# stepper.net
KiCad netlist of a schematic drawn in Altium Designer
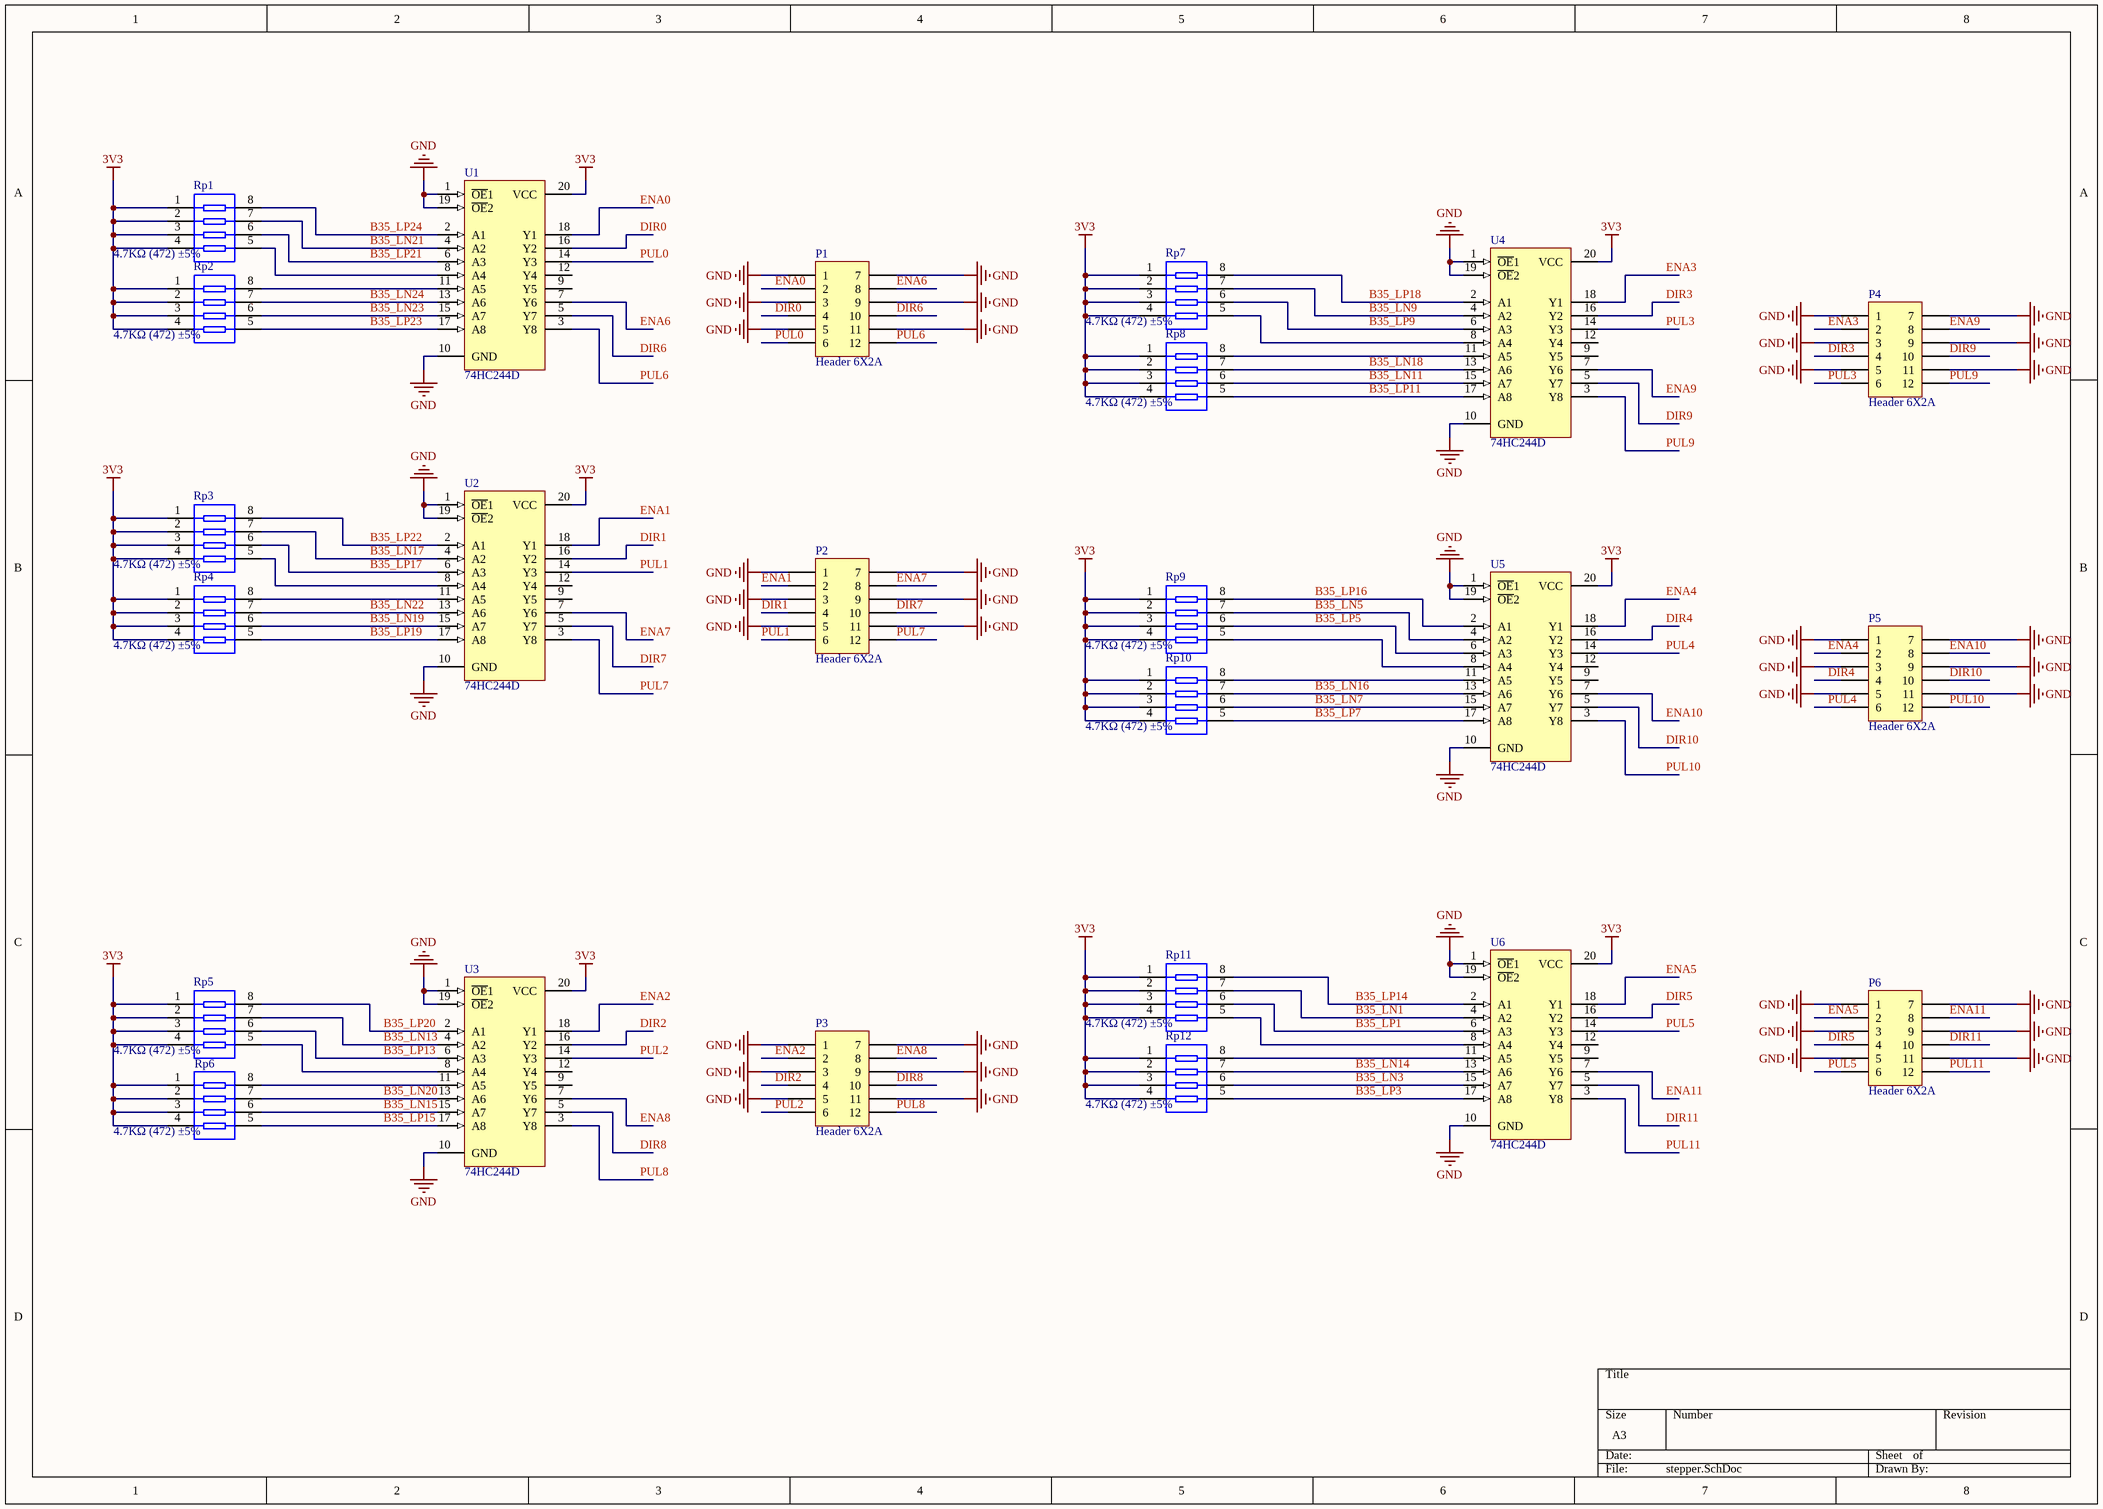
[diagram p0: stepper.SchDoc]

(export (version "E")
  (design (tool "Eeschema 10.0.6"))
  (components
    (comp (ref "P1")
      (value "Header 6X2A")
      (footprint "2EDG-3.81-06P*2 - duplicate")
      (description "Header, 6-Pin, Dual row")
      (fields (field (name "PUBLISHER") "Altium Limited"))
      (libsource (lib "Miscellaneous Connectors") (part "Header 6X2A"))
    )
    (comp (ref "P2")
      (value "Header 6X2A")
      (footprint "2EDG-3.81-06P*2 - duplicate")
      (description "Header, 6-Pin, Dual row")
      (fields (field (name "PUBLISHER") "Altium Limited"))
      (libsource (lib "Miscellaneous Connectors") (part "Header 6X2A"))
    )
    (comp (ref "P3")
      (value "Header 6X2A")
      (footprint "2EDG-3.81-06P*2 - duplicate")
      (description "Header, 6-Pin, Dual row")
      (fields (field (name "PUBLISHER") "Altium Limited"))
      (libsource (lib "Miscellaneous Connectors") (part "Header 6X2A"))
    )
    (comp (ref "P4")
      (value "Header 6X2A")
      (footprint "2EDG-3.81-06P*2 - duplicate")
      (description "Header, 6-Pin, Dual row")
      (fields (field (name "PUBLISHER") "Altium Limited"))
      (libsource (lib "Miscellaneous Connectors") (part "Header 6X2A"))
    )
    (comp (ref "P5")
      (value "Header 6X2A")
      (footprint "2EDG-3.81-06P*2 - duplicate")
      (description "Header, 6-Pin, Dual row")
      (fields (field (name "PUBLISHER") "Altium Limited"))
      (libsource (lib "Miscellaneous Connectors") (part "Header 6X2A"))
    )
    (comp (ref "P6")
      (value "Header 6X2A")
      (footprint "2EDG-3.81-06P*2 - duplicate")
      (description "Header, 6-Pin, Dual row")
      (fields (field (name "PUBLISHER") "Altium Limited"))
      (libsource (lib "Miscellaneous Connectors") (part "Header 6X2A"))
    )
    (comp (ref "Rp1")
      (value "4.7KΩ (472) ±5%")
      (footprint "0603_Rx4")
      (description "贴片排阻")
      (libsource (lib "Miscellaneous Devices LC") (part "0603*4  4.7KΩ (472) 5%"))
    )
    (comp (ref "Rp2")
      (value "4.7KΩ (472) ±5%")
      (footprint "0603_Rx4")
      (description "贴片排阻")
      (libsource (lib "Miscellaneous Devices LC") (part "0603*4  4.7KΩ (472) 5%"))
    )
    (comp (ref "Rp3")
      (value "4.7KΩ (472) ±5%")
      (footprint "0603_Rx4")
      (description "贴片排阻")
      (libsource (lib "Miscellaneous Devices LC") (part "0603*4  4.7KΩ (472) 5%"))
    )
    (comp (ref "Rp4")
      (value "4.7KΩ (472) ±5%")
      (footprint "0603_Rx4")
      (description "贴片排阻")
      (libsource (lib "Miscellaneous Devices LC") (part "0603*4  4.7KΩ (472) 5%"))
    )
    (comp (ref "Rp5")
      (value "4.7KΩ (472) ±5%")
      (footprint "0603_Rx4")
      (description "贴片排阻")
      (libsource (lib "Miscellaneous Devices LC") (part "0603*4  4.7KΩ (472) 5%"))
    )
    (comp (ref "Rp6")
      (value "4.7KΩ (472) ±5%")
      (footprint "0603_Rx4")
      (description "贴片排阻")
      (libsource (lib "Miscellaneous Devices LC") (part "0603*4  4.7KΩ (472) 5%"))
    )
    (comp (ref "Rp7")
      (value "4.7KΩ (472) ±5%")
      (footprint "0603_Rx4")
      (description "贴片排阻")
      (libsource (lib "Miscellaneous Devices LC") (part "0603*4  4.7KΩ (472) 5%"))
    )
    (comp (ref "Rp8")
      (value "4.7KΩ (472) ±5%")
      (footprint "0603_Rx4")
      (description "贴片排阻")
      (libsource (lib "Miscellaneous Devices LC") (part "0603*4  4.7KΩ (472) 5%"))
    )
    (comp (ref "Rp9")
      (value "4.7KΩ (472) ±5%")
      (footprint "0603_Rx4")
      (description "贴片排阻")
      (libsource (lib "Miscellaneous Devices LC") (part "0603*4  4.7KΩ (472) 5%"))
    )
    (comp (ref "Rp10")
      (value "4.7KΩ (472) ±5%")
      (footprint "0603_Rx4")
      (description "贴片排阻")
      (libsource (lib "Miscellaneous Devices LC") (part "0603*4  4.7KΩ (472) 5%"))
    )
    (comp (ref "Rp11")
      (value "4.7KΩ (472) ±5%")
      (footprint "0603_Rx4")
      (description "贴片排阻")
      (libsource (lib "Miscellaneous Devices LC") (part "0603*4  4.7KΩ (472) 5%"))
    )
    (comp (ref "Rp12")
      (value "4.7KΩ (472) ±5%")
      (footprint "0603_Rx4")
      (description "贴片排阻")
      (libsource (lib "Miscellaneous Devices LC") (part "0603*4  4.7KΩ (472) 5%"))
    )
    (comp (ref "U1")
      (value "74HC244D")
      (footprint "SOIC-20_300mil")
      (description "74系列逻辑芯片")
      (libsource (lib "Miscellaneous Devices LC") (part "74HC244D_[C5622]"))
    )
    (comp (ref "U2")
      (value "74HC244D")
      (footprint "SOIC-20_300mil")
      (description "74系列逻辑芯片")
      (libsource (lib "Miscellaneous Devices LC") (part "74HC244D_[C5622]"))
    )
    (comp (ref "U3")
      (value "74HC244D")
      (footprint "SOIC-20_300mil")
      (description "74系列逻辑芯片")
      (libsource (lib "Miscellaneous Devices LC") (part "74HC244D_[C5622]"))
    )
    (comp (ref "U4")
      (value "74HC244D")
      (footprint "SOIC-20_300mil")
      (description "74系列逻辑芯片")
      (libsource (lib "Miscellaneous Devices LC") (part "74HC244D_[C5622]"))
    )
    (comp (ref "U5")
      (value "74HC244D")
      (footprint "SOIC-20_300mil")
      (description "74系列逻辑芯片")
      (libsource (lib "Miscellaneous Devices LC") (part "74HC244D_[C5622]"))
    )
    (comp (ref "U6")
      (value "74HC244D")
      (footprint "SOIC-20_300mil")
      (description "74系列逻辑芯片")
      (libsource (lib "Miscellaneous Devices LC") (part "74HC244D_[C5622]"))
    )
  )
  (nets
    (net (code "1") (name "/B35_LN1") (class "Default")
      (node (ref "Rp11") (pin "7") (pinfunction "7_7") (pintype "passive"))
      (node (ref "U6") (pin "4") (pinfunction "A2_4") (pintype "input"))
    )
    (net (code "2") (name "/B35_LN3") (class "Default")
      (node (ref "Rp12") (pin "6") (pinfunction "6_6") (pintype "passive"))
      (node (ref "U6") (pin "15") (pinfunction "A7_15") (pintype "input"))
    )
    (net (code "3") (name "/B35_LN5") (class "Default")
      (node (ref "Rp9") (pin "7") (pinfunction "7_7") (pintype "passive"))
      (node (ref "U5") (pin "4") (pinfunction "A2_4") (pintype "input"))
    )
    (net (code "4") (name "/B35_LN7") (class "Default")
      (node (ref "Rp10") (pin "6") (pinfunction "6_6") (pintype "passive"))
      (node (ref "U5") (pin "15") (pinfunction "A7_15") (pintype "input"))
    )
    (net (code "5") (name "/B35_LN9") (class "Default")
      (node (ref "Rp7") (pin "7") (pinfunction "7_7") (pintype "passive"))
      (node (ref "U4") (pin "4") (pinfunction "A2_4") (pintype "input"))
    )
    (net (code "6") (name "/B35_LN11") (class "Default")
      (node (ref "Rp8") (pin "6") (pinfunction "6_6") (pintype "passive"))
      (node (ref "U4") (pin "15") (pinfunction "A7_15") (pintype "input"))
    )
    (net (code "7") (name "/B35_LN13") (class "Default")
      (node (ref "Rp5") (pin "7") (pinfunction "7_7") (pintype "passive"))
      (node (ref "U3") (pin "4") (pinfunction "A2_4") (pintype "input"))
    )
    (net (code "8") (name "/B35_LN14") (class "Default")
      (node (ref "Rp12") (pin "7") (pinfunction "7_7") (pintype "passive"))
      (node (ref "U6") (pin "13") (pinfunction "A6_13") (pintype "input"))
    )
    (net (code "9") (name "/B35_LN15") (class "Default")
      (node (ref "Rp6") (pin "6") (pinfunction "6_6") (pintype "passive"))
      (node (ref "U3") (pin "15") (pinfunction "A7_15") (pintype "input"))
    )
    (net (code "10") (name "/B35_LN16") (class "Default")
      (node (ref "Rp10") (pin "7") (pinfunction "7_7") (pintype "passive"))
      (node (ref "U5") (pin "13") (pinfunction "A6_13") (pintype "input"))
    )
    (net (code "11") (name "/B35_LN17") (class "Default")
      (node (ref "Rp3") (pin "7") (pinfunction "7_7") (pintype "passive"))
      (node (ref "U2") (pin "4") (pinfunction "A2_4") (pintype "input"))
    )
    (net (code "12") (name "/B35_LN18") (class "Default")
      (node (ref "Rp8") (pin "7") (pinfunction "7_7") (pintype "passive"))
      (node (ref "U4") (pin "13") (pinfunction "A6_13") (pintype "input"))
    )
    (net (code "13") (name "/B35_LN19") (class "Default")
      (node (ref "Rp4") (pin "6") (pinfunction "6_6") (pintype "passive"))
      (node (ref "U2") (pin "15") (pinfunction "A7_15") (pintype "input"))
    )
    (net (code "14") (name "/B35_LN20") (class "Default")
      (node (ref "Rp6") (pin "7") (pinfunction "7_7") (pintype "passive"))
      (node (ref "U3") (pin "13") (pinfunction "A6_13") (pintype "input"))
    )
    (net (code "15") (name "/B35_LN21") (class "Default")
      (node (ref "Rp1") (pin "7") (pinfunction "7_7") (pintype "passive"))
      (node (ref "U1") (pin "4") (pinfunction "A2_4") (pintype "input"))
    )
    (net (code "16") (name "/B35_LN22") (class "Default")
      (node (ref "Rp4") (pin "7") (pinfunction "7_7") (pintype "passive"))
      (node (ref "U2") (pin "13") (pinfunction "A6_13") (pintype "input"))
    )
    (net (code "17") (name "/B35_LN23") (class "Default")
      (node (ref "Rp2") (pin "6") (pinfunction "6_6") (pintype "passive"))
      (node (ref "U1") (pin "15") (pinfunction "A7_15") (pintype "input"))
    )
    (net (code "18") (name "/B35_LN24") (class "Default")
      (node (ref "Rp2") (pin "7") (pinfunction "7_7") (pintype "passive"))
      (node (ref "U1") (pin "13") (pinfunction "A6_13") (pintype "input"))
    )
    (net (code "19") (name "/B35_LP1") (class "Default")
      (node (ref "Rp11") (pin "6") (pinfunction "6_6") (pintype "passive"))
      (node (ref "U6") (pin "6") (pinfunction "A3_6") (pintype "input"))
    )
    (net (code "20") (name "/B35_LP3") (class "Default")
      (node (ref "Rp12") (pin "5") (pinfunction "5_5") (pintype "passive"))
      (node (ref "U6") (pin "17") (pinfunction "A8_17") (pintype "input"))
    )
    (net (code "21") (name "/B35_LP5") (class "Default")
      (node (ref "Rp9") (pin "6") (pinfunction "6_6") (pintype "passive"))
      (node (ref "U5") (pin "6") (pinfunction "A3_6") (pintype "input"))
    )
    (net (code "22") (name "/B35_LP7") (class "Default")
      (node (ref "Rp10") (pin "5") (pinfunction "5_5") (pintype "passive"))
      (node (ref "U5") (pin "17") (pinfunction "A8_17") (pintype "input"))
    )
    (net (code "23") (name "/B35_LP9") (class "Default")
      (node (ref "Rp7") (pin "6") (pinfunction "6_6") (pintype "passive"))
      (node (ref "U4") (pin "6") (pinfunction "A3_6") (pintype "input"))
    )
    (net (code "24") (name "/B35_LP11") (class "Default")
      (node (ref "Rp8") (pin "5") (pinfunction "5_5") (pintype "passive"))
      (node (ref "U4") (pin "17") (pinfunction "A8_17") (pintype "input"))
    )
    (net (code "25") (name "/B35_LP13") (class "Default")
      (node (ref "Rp5") (pin "6") (pinfunction "6_6") (pintype "passive"))
      (node (ref "U3") (pin "6") (pinfunction "A3_6") (pintype "input"))
    )
    (net (code "26") (name "/B35_LP14") (class "Default")
      (node (ref "Rp11") (pin "8") (pinfunction "8_8") (pintype "passive"))
      (node (ref "U6") (pin "2") (pinfunction "A1_2") (pintype "input"))
    )
    (net (code "27") (name "/B35_LP15") (class "Default")
      (node (ref "Rp6") (pin "5") (pinfunction "5_5") (pintype "passive"))
      (node (ref "U3") (pin "17") (pinfunction "A8_17") (pintype "input"))
    )
    (net (code "28") (name "/B35_LP16") (class "Default")
      (node (ref "Rp9") (pin "8") (pinfunction "8_8") (pintype "passive"))
      (node (ref "U5") (pin "2") (pinfunction "A1_2") (pintype "input"))
    )
    (net (code "29") (name "/B35_LP17") (class "Default")
      (node (ref "Rp3") (pin "6") (pinfunction "6_6") (pintype "passive"))
      (node (ref "U2") (pin "6") (pinfunction "A3_6") (pintype "input"))
    )
    (net (code "30") (name "/B35_LP18") (class "Default")
      (node (ref "Rp7") (pin "8") (pinfunction "8_8") (pintype "passive"))
      (node (ref "U4") (pin "2") (pinfunction "A1_2") (pintype "input"))
    )
    (net (code "31") (name "/B35_LP19") (class "Default")
      (node (ref "Rp4") (pin "5") (pinfunction "5_5") (pintype "passive"))
      (node (ref "U2") (pin "17") (pinfunction "A8_17") (pintype "input"))
    )
    (net (code "32") (name "/B35_LP20") (class "Default")
      (node (ref "Rp5") (pin "8") (pinfunction "8_8") (pintype "passive"))
      (node (ref "U3") (pin "2") (pinfunction "A1_2") (pintype "input"))
    )
    (net (code "33") (name "/B35_LP21") (class "Default")
      (node (ref "Rp1") (pin "6") (pinfunction "6_6") (pintype "passive"))
      (node (ref "U1") (pin "6") (pinfunction "A3_6") (pintype "input"))
    )
    (net (code "34") (name "/B35_LP22") (class "Default")
      (node (ref "Rp3") (pin "8") (pinfunction "8_8") (pintype "passive"))
      (node (ref "U2") (pin "2") (pinfunction "A1_2") (pintype "input"))
    )
    (net (code "35") (name "/B35_LP23") (class "Default")
      (node (ref "Rp2") (pin "5") (pinfunction "5_5") (pintype "passive"))
      (node (ref "U1") (pin "17") (pinfunction "A8_17") (pintype "input"))
    )
    (net (code "36") (name "/B35_LP24") (class "Default")
      (node (ref "Rp1") (pin "8") (pinfunction "8_8") (pintype "passive"))
      (node (ref "U1") (pin "2") (pinfunction "A1_2") (pintype "input"))
    )
    (net (code "37") (name "/DIR0") (class "Default")
      (node (ref "P1") (pin "4") (pinfunction "4_4") (pintype "passive"))
      (node (ref "U1") (pin "16") (pinfunction "Y2_16") (pintype "tri_state"))
    )
    (net (code "38") (name "/DIR1") (class "Default")
      (node (ref "P2") (pin "4") (pinfunction "4_4") (pintype "passive"))
      (node (ref "U2") (pin "16") (pinfunction "Y2_16") (pintype "tri_state"))
    )
    (net (code "39") (name "/DIR2") (class "Default")
      (node (ref "P3") (pin "4") (pinfunction "4_4") (pintype "passive"))
      (node (ref "U3") (pin "16") (pinfunction "Y2_16") (pintype "tri_state"))
    )
    (net (code "40") (name "/DIR3") (class "Default")
      (node (ref "P4") (pin "4") (pinfunction "4_4") (pintype "passive"))
      (node (ref "U4") (pin "16") (pinfunction "Y2_16") (pintype "tri_state"))
    )
    (net (code "41") (name "/DIR4") (class "Default")
      (node (ref "P5") (pin "4") (pinfunction "4_4") (pintype "passive"))
      (node (ref "U5") (pin "16") (pinfunction "Y2_16") (pintype "tri_state"))
    )
    (net (code "42") (name "/DIR5") (class "Default")
      (node (ref "P6") (pin "4") (pinfunction "4_4") (pintype "passive"))
      (node (ref "U6") (pin "16") (pinfunction "Y2_16") (pintype "tri_state"))
    )
    (net (code "43") (name "/DIR6") (class "Default")
      (node (ref "P1") (pin "10") (pinfunction "10_10") (pintype "passive"))
      (node (ref "U1") (pin "5") (pinfunction "Y7_5") (pintype "tri_state"))
    )
    (net (code "44") (name "/DIR7") (class "Default")
      (node (ref "P2") (pin "10") (pinfunction "10_10") (pintype "passive"))
      (node (ref "U2") (pin "5") (pinfunction "Y7_5") (pintype "tri_state"))
    )
    (net (code "45") (name "/DIR8") (class "Default")
      (node (ref "P3") (pin "10") (pinfunction "10_10") (pintype "passive"))
      (node (ref "U3") (pin "5") (pinfunction "Y7_5") (pintype "tri_state"))
    )
    (net (code "46") (name "/DIR9") (class "Default")
      (node (ref "P4") (pin "10") (pinfunction "10_10") (pintype "passive"))
      (node (ref "U4") (pin "5") (pinfunction "Y7_5") (pintype "tri_state"))
    )
    (net (code "47") (name "/DIR10") (class "Default")
      (node (ref "P5") (pin "10") (pinfunction "10_10") (pintype "passive"))
      (node (ref "U5") (pin "5") (pinfunction "Y7_5") (pintype "tri_state"))
    )
    (net (code "48") (name "/DIR11") (class "Default")
      (node (ref "P6") (pin "10") (pinfunction "10_10") (pintype "passive"))
      (node (ref "U6") (pin "5") (pinfunction "Y7_5") (pintype "tri_state"))
    )
    (net (code "49") (name "/ENA0") (class "Default")
      (node (ref "P1") (pin "2") (pinfunction "2_2") (pintype "passive"))
      (node (ref "U1") (pin "18") (pinfunction "Y1_18") (pintype "tri_state"))
    )
    (net (code "50") (name "/ENA1") (class "Default")
      (node (ref "P2") (pin "2") (pinfunction "2_2") (pintype "passive"))
      (node (ref "U2") (pin "18") (pinfunction "Y1_18") (pintype "tri_state"))
    )
    (net (code "51") (name "/ENA2") (class "Default")
      (node (ref "P3") (pin "2") (pinfunction "2_2") (pintype "passive"))
      (node (ref "U3") (pin "18") (pinfunction "Y1_18") (pintype "tri_state"))
    )
    (net (code "52") (name "/ENA3") (class "Default")
      (node (ref "P4") (pin "2") (pinfunction "2_2") (pintype "passive"))
      (node (ref "U4") (pin "18") (pinfunction "Y1_18") (pintype "tri_state"))
    )
    (net (code "53") (name "/ENA4") (class "Default")
      (node (ref "P5") (pin "2") (pinfunction "2_2") (pintype "passive"))
      (node (ref "U5") (pin "18") (pinfunction "Y1_18") (pintype "tri_state"))
    )
    (net (code "54") (name "/ENA5") (class "Default")
      (node (ref "P6") (pin "2") (pinfunction "2_2") (pintype "passive"))
      (node (ref "U6") (pin "18") (pinfunction "Y1_18") (pintype "tri_state"))
    )
    (net (code "55") (name "/ENA6") (class "Default")
      (node (ref "P1") (pin "8") (pinfunction "8_8") (pintype "passive"))
      (node (ref "U1") (pin "7") (pinfunction "Y6_7") (pintype "tri_state"))
    )
    (net (code "56") (name "/ENA7") (class "Default")
      (node (ref "P2") (pin "8") (pinfunction "8_8") (pintype "passive"))
      (node (ref "U2") (pin "7") (pinfunction "Y6_7") (pintype "tri_state"))
    )
    (net (code "57") (name "/ENA8") (class "Default")
      (node (ref "P3") (pin "8") (pinfunction "8_8") (pintype "passive"))
      (node (ref "U3") (pin "7") (pinfunction "Y6_7") (pintype "tri_state"))
    )
    (net (code "58") (name "/ENA9") (class "Default")
      (node (ref "P4") (pin "8") (pinfunction "8_8") (pintype "passive"))
      (node (ref "U4") (pin "7") (pinfunction "Y6_7") (pintype "tri_state"))
    )
    (net (code "59") (name "/ENA10") (class "Default")
      (node (ref "P5") (pin "8") (pinfunction "8_8") (pintype "passive"))
      (node (ref "U5") (pin "7") (pinfunction "Y6_7") (pintype "tri_state"))
    )
    (net (code "60") (name "/ENA11") (class "Default")
      (node (ref "P6") (pin "8") (pinfunction "8_8") (pintype "passive"))
      (node (ref "U6") (pin "7") (pinfunction "Y6_7") (pintype "tri_state"))
    )
    (net (code "61") (name "/PUL0") (class "Default")
      (node (ref "P1") (pin "6") (pinfunction "6_6") (pintype "passive"))
      (node (ref "U1") (pin "14") (pinfunction "Y3_14") (pintype "tri_state"))
    )
    (net (code "62") (name "/PUL1") (class "Default")
      (node (ref "P2") (pin "6") (pinfunction "6_6") (pintype "passive"))
      (node (ref "U2") (pin "14") (pinfunction "Y3_14") (pintype "tri_state"))
    )
    (net (code "63") (name "/PUL2") (class "Default")
      (node (ref "P3") (pin "6") (pinfunction "6_6") (pintype "passive"))
      (node (ref "U3") (pin "14") (pinfunction "Y3_14") (pintype "tri_state"))
    )
    (net (code "64") (name "/PUL3") (class "Default")
      (node (ref "P4") (pin "6") (pinfunction "6_6") (pintype "passive"))
      (node (ref "U4") (pin "14") (pinfunction "Y3_14") (pintype "tri_state"))
    )
    (net (code "65") (name "/PUL4") (class "Default")
      (node (ref "P5") (pin "6") (pinfunction "6_6") (pintype "passive"))
      (node (ref "U5") (pin "14") (pinfunction "Y3_14") (pintype "tri_state"))
    )
    (net (code "66") (name "/PUL5") (class "Default")
      (node (ref "P6") (pin "6") (pinfunction "6_6") (pintype "passive"))
      (node (ref "U6") (pin "14") (pinfunction "Y3_14") (pintype "tri_state"))
    )
    (net (code "67") (name "/PUL6") (class "Default")
      (node (ref "P1") (pin "12") (pinfunction "12_12") (pintype "passive"))
      (node (ref "U1") (pin "3") (pinfunction "Y8_3") (pintype "tri_state"))
    )
    (net (code "68") (name "/PUL7") (class "Default")
      (node (ref "P2") (pin "12") (pinfunction "12_12") (pintype "passive"))
      (node (ref "U2") (pin "3") (pinfunction "Y8_3") (pintype "tri_state"))
    )
    (net (code "69") (name "/PUL8") (class "Default")
      (node (ref "P3") (pin "12") (pinfunction "12_12") (pintype "passive"))
      (node (ref "U3") (pin "3") (pinfunction "Y8_3") (pintype "tri_state"))
    )
    (net (code "70") (name "/PUL9") (class "Default")
      (node (ref "P4") (pin "12") (pinfunction "12_12") (pintype "passive"))
      (node (ref "U4") (pin "3") (pinfunction "Y8_3") (pintype "tri_state"))
    )
    (net (code "71") (name "/PUL10") (class "Default")
      (node (ref "P5") (pin "12") (pinfunction "12_12") (pintype "passive"))
      (node (ref "U5") (pin "3") (pinfunction "Y8_3") (pintype "tri_state"))
    )
    (net (code "72") (name "/PUL11") (class "Default")
      (node (ref "P6") (pin "12") (pinfunction "12_12") (pintype "passive"))
      (node (ref "U6") (pin "3") (pinfunction "Y8_3") (pintype "tri_state"))
    )
    (net (code "73") (name "3V3") (class "Default")
      (node (ref "Rp1") (pin "1") (pinfunction "1_1") (pintype "passive"))
      (node (ref "Rp1") (pin "2") (pinfunction "2_2") (pintype "passive"))
      (node (ref "Rp1") (pin "3") (pinfunction "3_3") (pintype "passive"))
      (node (ref "Rp1") (pin "4") (pinfunction "4_4") (pintype "passive"))
      (node (ref "Rp10") (pin "1") (pinfunction "1_1") (pintype "passive"))
      (node (ref "Rp10") (pin "2") (pinfunction "2_2") (pintype "passive"))
      (node (ref "Rp10") (pin "3") (pinfunction "3_3") (pintype "passive"))
      (node (ref "Rp10") (pin "4") (pinfunction "4_4") (pintype "passive"))
      (node (ref "Rp11") (pin "1") (pinfunction "1_1") (pintype "passive"))
      (node (ref "Rp11") (pin "2") (pinfunction "2_2") (pintype "passive"))
      (node (ref "Rp11") (pin "3") (pinfunction "3_3") (pintype "passive"))
      (node (ref "Rp11") (pin "4") (pinfunction "4_4") (pintype "passive"))
      (node (ref "Rp12") (pin "1") (pinfunction "1_1") (pintype "passive"))
      (node (ref "Rp12") (pin "2") (pinfunction "2_2") (pintype "passive"))
      (node (ref "Rp12") (pin "3") (pinfunction "3_3") (pintype "passive"))
      (node (ref "Rp12") (pin "4") (pinfunction "4_4") (pintype "passive"))
      (node (ref "Rp2") (pin "1") (pinfunction "1_1") (pintype "passive"))
      (node (ref "Rp2") (pin "2") (pinfunction "2_2") (pintype "passive"))
      (node (ref "Rp2") (pin "3") (pinfunction "3_3") (pintype "passive"))
      (node (ref "Rp2") (pin "4") (pinfunction "4_4") (pintype "passive"))
      (node (ref "Rp3") (pin "1") (pinfunction "1_1") (pintype "passive"))
      (node (ref "Rp3") (pin "2") (pinfunction "2_2") (pintype "passive"))
      (node (ref "Rp3") (pin "3") (pinfunction "3_3") (pintype "passive"))
      (node (ref "Rp3") (pin "4") (pinfunction "4_4") (pintype "passive"))
      (node (ref "Rp4") (pin "1") (pinfunction "1_1") (pintype "passive"))
      (node (ref "Rp4") (pin "2") (pinfunction "2_2") (pintype "passive"))
      (node (ref "Rp4") (pin "3") (pinfunction "3_3") (pintype "passive"))
      (node (ref "Rp4") (pin "4") (pinfunction "4_4") (pintype "passive"))
      (node (ref "Rp5") (pin "1") (pinfunction "1_1") (pintype "passive"))
      (node (ref "Rp5") (pin "2") (pinfunction "2_2") (pintype "passive"))
      (node (ref "Rp5") (pin "3") (pinfunction "3_3") (pintype "passive"))
      (node (ref "Rp5") (pin "4") (pinfunction "4_4") (pintype "passive"))
      (node (ref "Rp6") (pin "1") (pinfunction "1_1") (pintype "passive"))
      (node (ref "Rp6") (pin "2") (pinfunction "2_2") (pintype "passive"))
      (node (ref "Rp6") (pin "3") (pinfunction "3_3") (pintype "passive"))
      (node (ref "Rp6") (pin "4") (pinfunction "4_4") (pintype "passive"))
      (node (ref "Rp7") (pin "1") (pinfunction "1_1") (pintype "passive"))
      (node (ref "Rp7") (pin "2") (pinfunction "2_2") (pintype "passive"))
      (node (ref "Rp7") (pin "3") (pinfunction "3_3") (pintype "passive"))
      (node (ref "Rp7") (pin "4") (pinfunction "4_4") (pintype "passive"))
      (node (ref "Rp8") (pin "1") (pinfunction "1_1") (pintype "passive"))
      (node (ref "Rp8") (pin "2") (pinfunction "2_2") (pintype "passive"))
      (node (ref "Rp8") (pin "3") (pinfunction "3_3") (pintype "passive"))
      (node (ref "Rp8") (pin "4") (pinfunction "4_4") (pintype "passive"))
      (node (ref "Rp9") (pin "1") (pinfunction "1_1") (pintype "passive"))
      (node (ref "Rp9") (pin "2") (pinfunction "2_2") (pintype "passive"))
      (node (ref "Rp9") (pin "3") (pinfunction "3_3") (pintype "passive"))
      (node (ref "Rp9") (pin "4") (pinfunction "4_4") (pintype "passive"))
      (node (ref "U1") (pin "20") (pinfunction "VCC_20") (pintype "power_in"))
      (node (ref "U2") (pin "20") (pinfunction "VCC_20") (pintype "power_in"))
      (node (ref "U3") (pin "20") (pinfunction "VCC_20") (pintype "power_in"))
      (node (ref "U4") (pin "20") (pinfunction "VCC_20") (pintype "power_in"))
      (node (ref "U5") (pin "20") (pinfunction "VCC_20") (pintype "power_in"))
      (node (ref "U6") (pin "20") (pinfunction "VCC_20") (pintype "power_in"))
    )
    (net (code "74") (name "GND") (class "Default")
      (node (ref "P1") (pin "1") (pinfunction "1_1") (pintype "passive"))
      (node (ref "P1") (pin "11") (pinfunction "11_11") (pintype "passive"))
      (node (ref "P1") (pin "3") (pinfunction "3_3") (pintype "passive"))
      (node (ref "P1") (pin "5") (pinfunction "5_5") (pintype "passive"))
      (node (ref "P1") (pin "7") (pinfunction "7_7") (pintype "passive"))
      (node (ref "P1") (pin "9") (pinfunction "9_9") (pintype "passive"))
      (node (ref "P2") (pin "1") (pinfunction "1_1") (pintype "passive"))
      (node (ref "P2") (pin "11") (pinfunction "11_11") (pintype "passive"))
      (node (ref "P2") (pin "3") (pinfunction "3_3") (pintype "passive"))
      (node (ref "P2") (pin "5") (pinfunction "5_5") (pintype "passive"))
      (node (ref "P2") (pin "7") (pinfunction "7_7") (pintype "passive"))
      (node (ref "P2") (pin "9") (pinfunction "9_9") (pintype "passive"))
      (node (ref "P3") (pin "1") (pinfunction "1_1") (pintype "passive"))
      (node (ref "P3") (pin "11") (pinfunction "11_11") (pintype "passive"))
      (node (ref "P3") (pin "3") (pinfunction "3_3") (pintype "passive"))
      (node (ref "P3") (pin "5") (pinfunction "5_5") (pintype "passive"))
      (node (ref "P3") (pin "7") (pinfunction "7_7") (pintype "passive"))
      (node (ref "P3") (pin "9") (pinfunction "9_9") (pintype "passive"))
      (node (ref "P4") (pin "1") (pinfunction "1_1") (pintype "passive"))
      (node (ref "P4") (pin "11") (pinfunction "11_11") (pintype "passive"))
      (node (ref "P4") (pin "3") (pinfunction "3_3") (pintype "passive"))
      (node (ref "P4") (pin "5") (pinfunction "5_5") (pintype "passive"))
      (node (ref "P4") (pin "7") (pinfunction "7_7") (pintype "passive"))
      (node (ref "P4") (pin "9") (pinfunction "9_9") (pintype "passive"))
      (node (ref "P5") (pin "1") (pinfunction "1_1") (pintype "passive"))
      (node (ref "P5") (pin "11") (pinfunction "11_11") (pintype "passive"))
      (node (ref "P5") (pin "3") (pinfunction "3_3") (pintype "passive"))
      (node (ref "P5") (pin "5") (pinfunction "5_5") (pintype "passive"))
      (node (ref "P5") (pin "7") (pinfunction "7_7") (pintype "passive"))
      (node (ref "P5") (pin "9") (pinfunction "9_9") (pintype "passive"))
      (node (ref "P6") (pin "1") (pinfunction "1_1") (pintype "passive"))
      (node (ref "P6") (pin "11") (pinfunction "11_11") (pintype "passive"))
      (node (ref "P6") (pin "3") (pinfunction "3_3") (pintype "passive"))
      (node (ref "P6") (pin "5") (pinfunction "5_5") (pintype "passive"))
      (node (ref "P6") (pin "7") (pinfunction "7_7") (pintype "passive"))
      (node (ref "P6") (pin "9") (pinfunction "9_9") (pintype "passive"))
      (node (ref "U1") (pin "1") (pinfunction "~{OE}1_1") (pintype "input"))
      (node (ref "U1") (pin "10") (pinfunction "GND_10") (pintype "power_in"))
      (node (ref "U1") (pin "19") (pinfunction "~{OE}2_19") (pintype "input"))
      (node (ref "U2") (pin "1") (pinfunction "~{OE}1_1") (pintype "input"))
      (node (ref "U2") (pin "10") (pinfunction "GND_10") (pintype "power_in"))
      (node (ref "U2") (pin "19") (pinfunction "~{OE}2_19") (pintype "input"))
      (node (ref "U3") (pin "1") (pinfunction "~{OE}1_1") (pintype "input"))
      (node (ref "U3") (pin "10") (pinfunction "GND_10") (pintype "power_in"))
      (node (ref "U3") (pin "19") (pinfunction "~{OE}2_19") (pintype "input"))
      (node (ref "U4") (pin "1") (pinfunction "~{OE}1_1") (pintype "input"))
      (node (ref "U4") (pin "10") (pinfunction "GND_10") (pintype "power_in"))
      (node (ref "U4") (pin "19") (pinfunction "~{OE}2_19") (pintype "input"))
      (node (ref "U5") (pin "1") (pinfunction "~{OE}1_1") (pintype "input"))
      (node (ref "U5") (pin "10") (pinfunction "GND_10") (pintype "power_in"))
      (node (ref "U5") (pin "19") (pinfunction "~{OE}2_19") (pintype "input"))
      (node (ref "U6") (pin "1") (pinfunction "~{OE}1_1") (pintype "input"))
      (node (ref "U6") (pin "10") (pinfunction "GND_10") (pintype "power_in"))
      (node (ref "U6") (pin "19") (pinfunction "~{OE}2_19") (pintype "input"))
    )
    (net (code "75") (name "Net-(U1-A4)") (class "Default")
      (node (ref "Rp1") (pin "5") (pinfunction "5_5") (pintype "passive"))
      (node (ref "U1") (pin "8") (pinfunction "A4_8") (pintype "input"))
    )
    (net (code "76") (name "Net-(U1-A5)") (class "Default")
      (node (ref "Rp2") (pin "8") (pinfunction "8_8") (pintype "passive"))
      (node (ref "U1") (pin "11") (pinfunction "A5_11") (pintype "input"))
    )
    (net (code "77") (name "Net-(U2-A4)") (class "Default")
      (node (ref "Rp3") (pin "5") (pinfunction "5_5") (pintype "passive"))
      (node (ref "U2") (pin "8") (pinfunction "A4_8") (pintype "input"))
    )
    (net (code "78") (name "Net-(U2-A5)") (class "Default")
      (node (ref "Rp4") (pin "8") (pinfunction "8_8") (pintype "passive"))
      (node (ref "U2") (pin "11") (pinfunction "A5_11") (pintype "input"))
    )
    (net (code "79") (name "Net-(U3-A4)") (class "Default")
      (node (ref "Rp5") (pin "5") (pinfunction "5_5") (pintype "passive"))
      (node (ref "U3") (pin "8") (pinfunction "A4_8") (pintype "input"))
    )
    (net (code "80") (name "Net-(U3-A5)") (class "Default")
      (node (ref "Rp6") (pin "8") (pinfunction "8_8") (pintype "passive"))
      (node (ref "U3") (pin "11") (pinfunction "A5_11") (pintype "input"))
    )
    (net (code "81") (name "Net-(U4-A4)") (class "Default")
      (node (ref "Rp7") (pin "5") (pinfunction "5_5") (pintype "passive"))
      (node (ref "U4") (pin "8") (pinfunction "A4_8") (pintype "input"))
    )
    (net (code "82") (name "Net-(U4-A5)") (class "Default")
      (node (ref "Rp8") (pin "8") (pinfunction "8_8") (pintype "passive"))
      (node (ref "U4") (pin "11") (pinfunction "A5_11") (pintype "input"))
    )
    (net (code "83") (name "Net-(U5-A4)") (class "Default")
      (node (ref "Rp9") (pin "5") (pinfunction "5_5") (pintype "passive"))
      (node (ref "U5") (pin "8") (pinfunction "A4_8") (pintype "input"))
    )
    (net (code "84") (name "Net-(U5-A5)") (class "Default")
      (node (ref "Rp10") (pin "8") (pinfunction "8_8") (pintype "passive"))
      (node (ref "U5") (pin "11") (pinfunction "A5_11") (pintype "input"))
    )
    (net (code "85") (name "Net-(U6-A4)") (class "Default")
      (node (ref "Rp11") (pin "5") (pinfunction "5_5") (pintype "passive"))
      (node (ref "U6") (pin "8") (pinfunction "A4_8") (pintype "input"))
    )
    (net (code "86") (name "Net-(U6-A5)") (class "Default")
      (node (ref "Rp12") (pin "8") (pinfunction "8_8") (pintype "passive"))
      (node (ref "U6") (pin "11") (pinfunction "A5_11") (pintype "input"))
    )
    (net (code "87") (name "unconnected-(U1-Y4-Pad12)") (class "Default")
      (node (ref "U1") (pin "12") (pinfunction "Y4_12") (pintype "tri_state"))
    )
    (net (code "88") (name "unconnected-(U1-Y5-Pad9)") (class "Default")
      (node (ref "U1") (pin "9") (pinfunction "Y5_9") (pintype "tri_state"))
    )
    (net (code "89") (name "unconnected-(U2-Y4-Pad12)") (class "Default")
      (node (ref "U2") (pin "12") (pinfunction "Y4_12") (pintype "tri_state"))
    )
    (net (code "90") (name "unconnected-(U2-Y5-Pad9)") (class "Default")
      (node (ref "U2") (pin "9") (pinfunction "Y5_9") (pintype "tri_state"))
    )
    (net (code "91") (name "unconnected-(U3-Y4-Pad12)") (class "Default")
      (node (ref "U3") (pin "12") (pinfunction "Y4_12") (pintype "tri_state"))
    )
    (net (code "92") (name "unconnected-(U3-Y5-Pad9)") (class "Default")
      (node (ref "U3") (pin "9") (pinfunction "Y5_9") (pintype "tri_state"))
    )
    (net (code "93") (name "unconnected-(U4-Y4-Pad12)") (class "Default")
      (node (ref "U4") (pin "12") (pinfunction "Y4_12") (pintype "tri_state"))
    )
    (net (code "94") (name "unconnected-(U4-Y5-Pad9)") (class "Default")
      (node (ref "U4") (pin "9") (pinfunction "Y5_9") (pintype "tri_state"))
    )
    (net (code "95") (name "unconnected-(U5-Y4-Pad12)") (class "Default")
      (node (ref "U5") (pin "12") (pinfunction "Y4_12") (pintype "tri_state"))
    )
    (net (code "96") (name "unconnected-(U5-Y5-Pad9)") (class "Default")
      (node (ref "U5") (pin "9") (pinfunction "Y5_9") (pintype "tri_state"))
    )
    (net (code "97") (name "unconnected-(U6-Y4-Pad12)") (class "Default")
      (node (ref "U6") (pin "12") (pinfunction "Y4_12") (pintype "tri_state"))
    )
    (net (code "98") (name "unconnected-(U6-Y5-Pad9)") (class "Default")
      (node (ref "U6") (pin "9") (pinfunction "Y5_9") (pintype "tri_state"))
    )
  )
)
